# STM32F407VET6.net
KiCad netlist of a schematic drawn in EasyEDA Pro
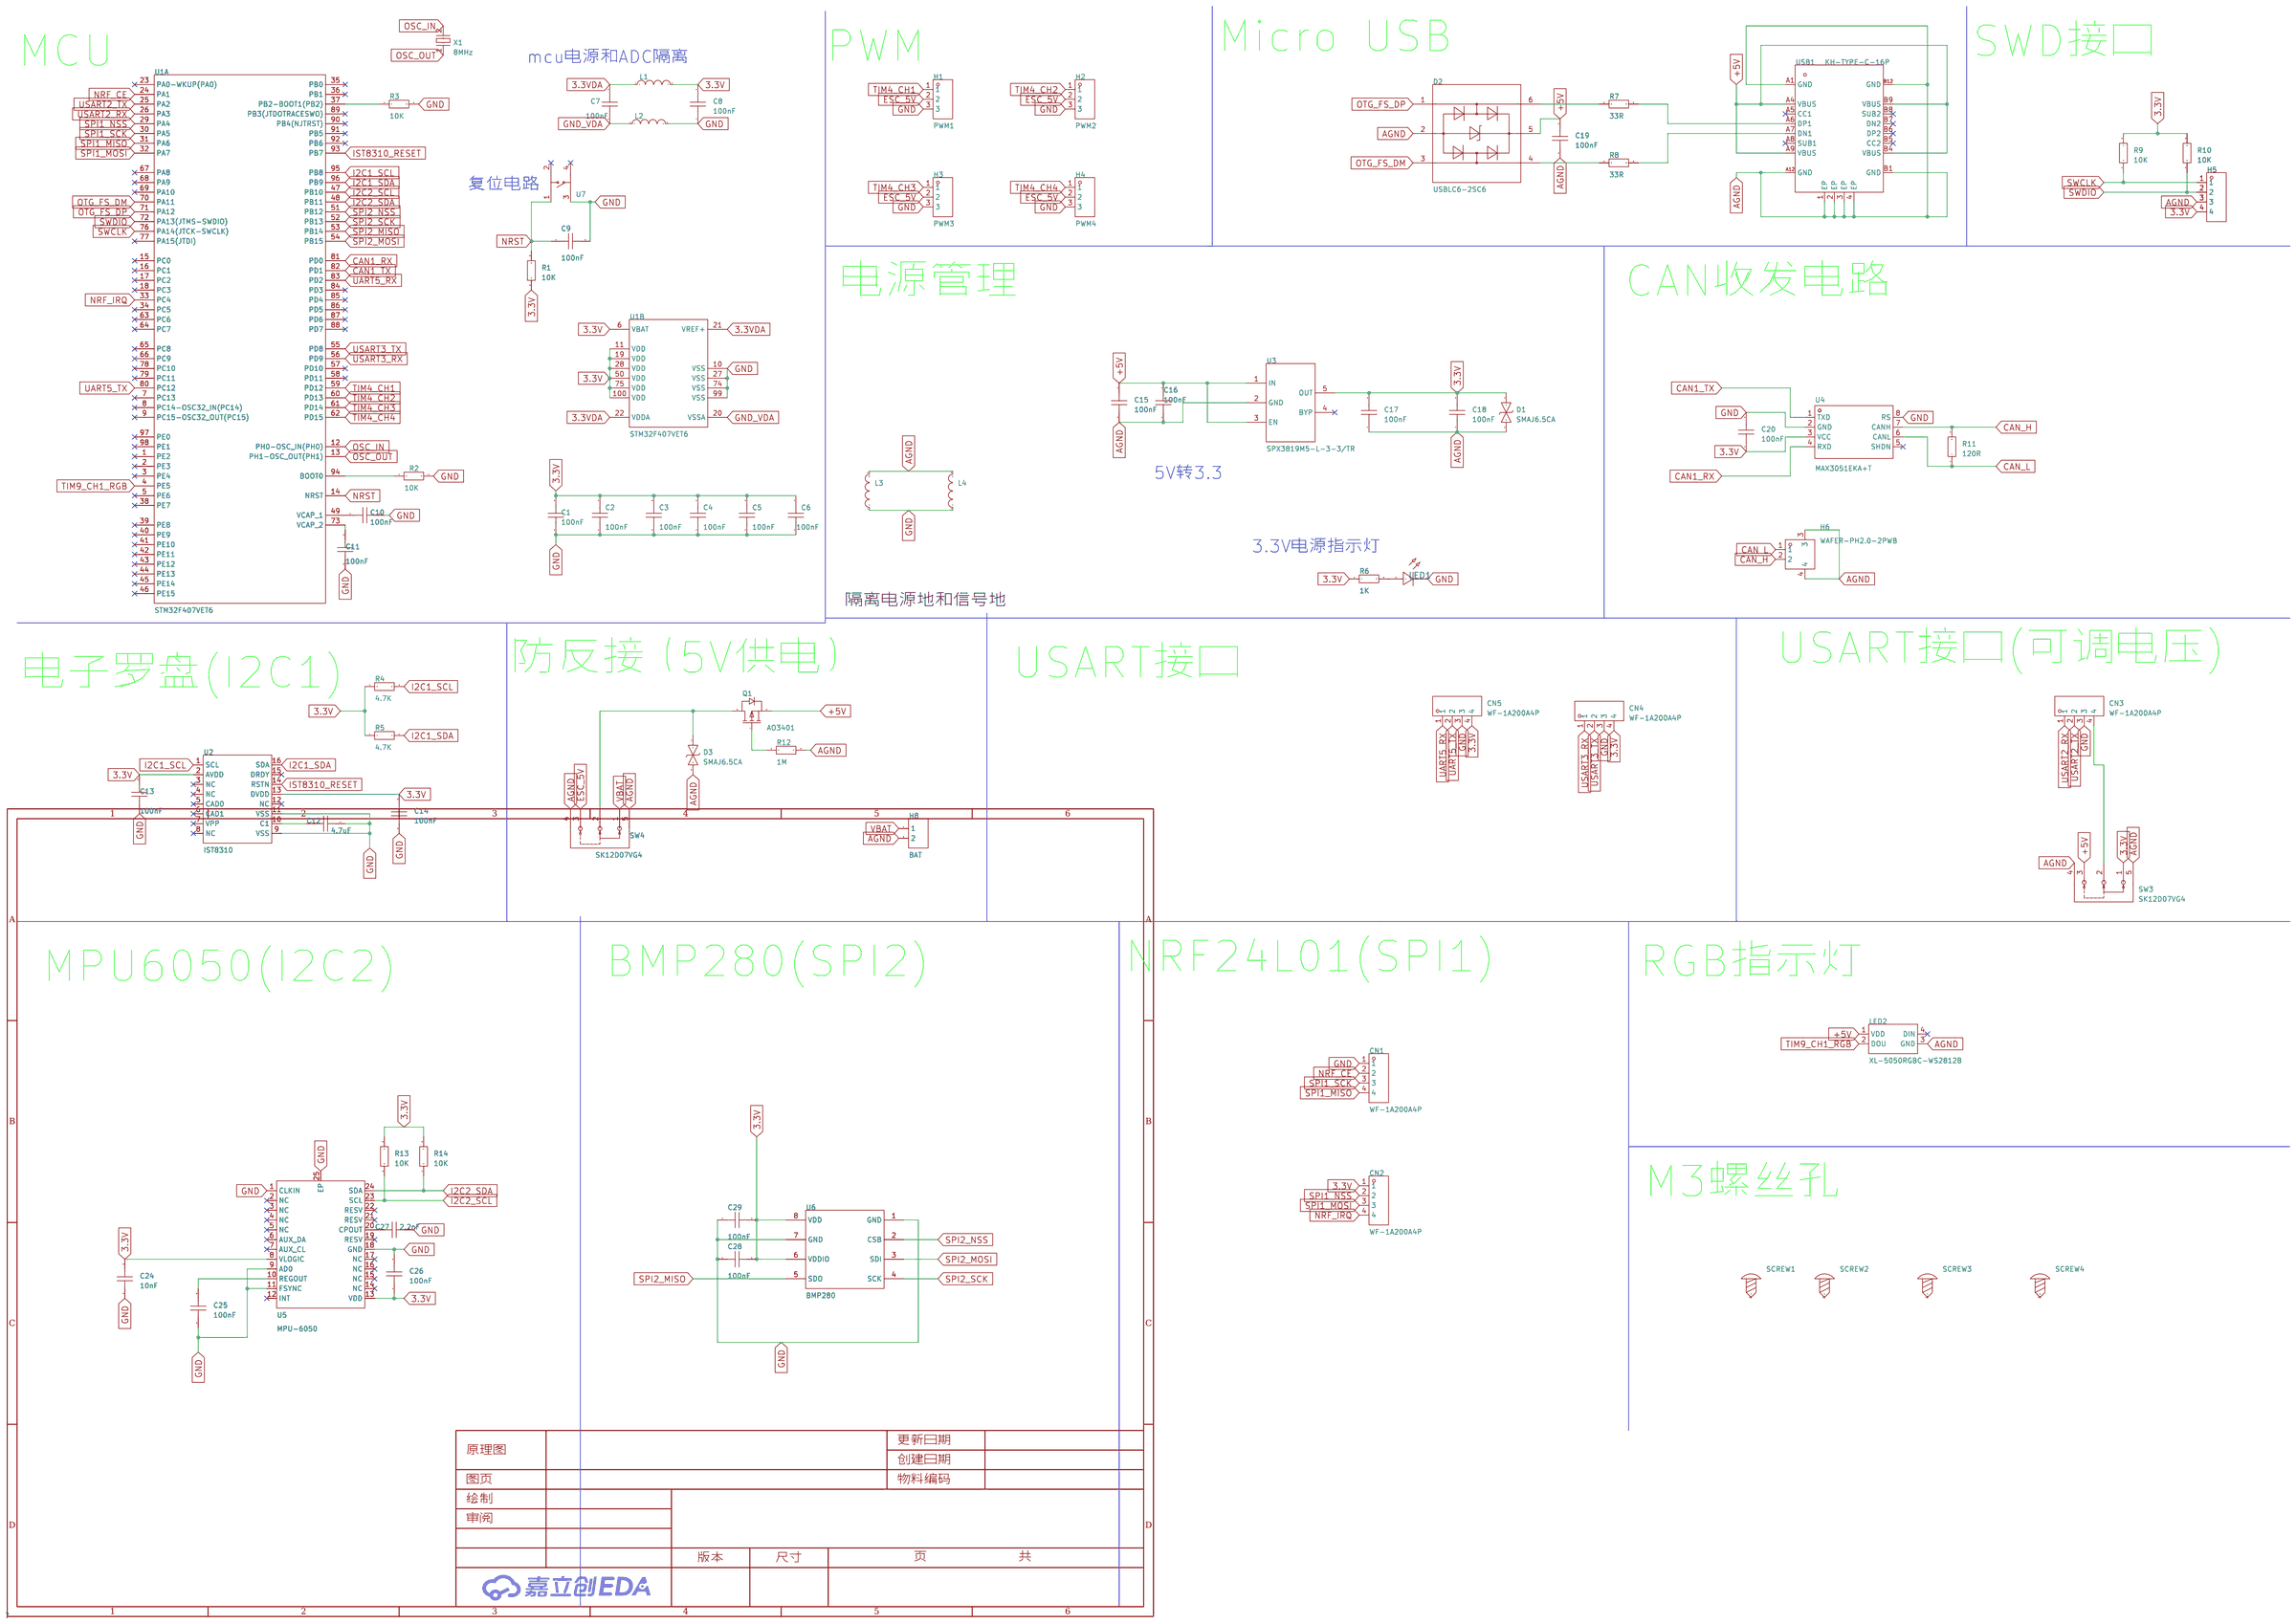
[diagram p0: schematic sheet]

(export (version "E")
  (design (tool "Eeschema 10.0.6"))
  (components
    (comp (ref "C1")
      (value "100nF")
      (footprint "easyedapro:C0603")
      (libsource (lib "easyedapro") (part "CapAcitance"))
    )
    (comp (ref "C2")
      (value "100nF")
      (footprint "easyedapro:C0603")
      (libsource (lib "easyedapro") (part "CapAcitance"))
    )
    (comp (ref "C3")
      (value "100nF")
      (footprint "easyedapro:C0603")
      (libsource (lib "easyedapro") (part "CapAcitance"))
    )
    (comp (ref "C4")
      (value "100nF")
      (footprint "easyedapro:C0603")
      (libsource (lib "easyedapro") (part "CapAcitance"))
    )
    (comp (ref "C5")
      (value "100nF")
      (footprint "easyedapro:C0603")
      (libsource (lib "easyedapro") (part "CapAcitance"))
    )
    (comp (ref "C6")
      (value "100nF")
      (footprint "easyedapro:C0603")
      (libsource (lib "easyedapro") (part "CapAcitance"))
    )
    (comp (ref "C7")
      (value "100nF")
      (footprint "easyedapro:C0603")
      (libsource (lib "easyedapro") (part "CapAcitance"))
    )
    (comp (ref "C8")
      (value "100nF")
      (footprint "easyedapro:C0603")
      (libsource (lib "easyedapro") (part "CapAcitance"))
    )
    (comp (ref "C9")
      (value "100nF")
      (footprint "easyedapro:C0603")
      (libsource (lib "easyedapro") (part "CapAcitance"))
    )
    (comp (ref "C10")
      (value "100nF")
      (footprint "easyedapro:C0603")
      (libsource (lib "easyedapro") (part "CapAcitance"))
    )
    (comp (ref "C11")
      (value "100nF")
      (footprint "easyedapro:C0603")
      (libsource (lib "easyedapro") (part "CapAcitance"))
    )
    (comp (ref "C12")
      (value "4.7uF")
      (footprint "easyedapro:C0603")
      (libsource (lib "easyedapro") (part "CapAcitance"))
    )
    (comp (ref "C13")
      (value "100nF")
      (footprint "easyedapro:C0603")
      (libsource (lib "easyedapro") (part "CapAcitance"))
    )
    (comp (ref "C14")
      (value "100nF")
      (footprint "easyedapro:C0603")
      (libsource (lib "easyedapro") (part "CapAcitance"))
    )
    (comp (ref "C15")
      (value "100nF")
      (footprint "easyedapro:C0603")
      (libsource (lib "easyedapro") (part "CapAcitance"))
    )
    (comp (ref "C16")
      (value "100nF")
      (footprint "easyedapro:C0603")
      (libsource (lib "easyedapro") (part "CapAcitance"))
    )
    (comp (ref "C17")
      (value "100nF")
      (footprint "easyedapro:C0603")
      (libsource (lib "easyedapro") (part "CapAcitance"))
    )
    (comp (ref "C18")
      (value "100nF")
      (footprint "easyedapro:C0603")
      (libsource (lib "easyedapro") (part "CapAcitance"))
    )
    (comp (ref "C19")
      (value "100nF")
      (footprint "easyedapro:C0603")
      (libsource (lib "easyedapro") (part "CapAcitance"))
    )
    (comp (ref "C20")
      (value "100nF")
      (footprint "easyedapro:C0603")
      (libsource (lib "easyedapro") (part "CapAcitance"))
    )
    (comp (ref "C24")
      (value "10nF")
      (footprint "easyedapro:C0603")
      (libsource (lib "easyedapro") (part "CapAcitance"))
    )
    (comp (ref "C25")
      (value "100nF")
      (footprint "easyedapro:C0603")
      (libsource (lib "easyedapro") (part "CapAcitance"))
    )
    (comp (ref "C26")
      (value "100nF")
      (footprint "easyedapro:C0603")
      (libsource (lib "easyedapro") (part "CapAcitance"))
    )
    (comp (ref "C27")
      (value "2.2nF")
      (footprint "easyedapro:C0603")
      (libsource (lib "easyedapro") (part "CapAcitance"))
    )
    (comp (ref "C28")
      (value "100nF")
      (footprint "easyedapro:C0603")
      (libsource (lib "easyedapro") (part "CapAcitance"))
    )
    (comp (ref "C29")
      (value "100nF")
      (footprint "easyedapro:C0603")
      (libsource (lib "easyedapro") (part "CapAcitance"))
    )
    (comp (ref "CN1")
      (value "WF-1A200A4P")
      (footprint "easyedapro:CONN-TH_4P-P2.00_PH2.0-4P-1")
      (description "插针结构:1x4P;间距:2mm;安装方式:直插;参考系列:PH;总PIN数:4P;排数:1;每排PIN数:4;额定电流:2A;触头材质:黄铜;触头镀层:锡;工作温度范围:-25°C~+85°C;")
      (fields (field (name "Manufacturer") "BXCONN(宝讯)"))
      (libsource (lib "easyedapro") (part "WF-1A200A4P"))
    )
    (comp (ref "CN2")
      (value "WF-1A200A4P")
      (footprint "easyedapro:CONN-TH_4P-P2.00_PH2.0-4P-1")
      (description "插针结构:1x4P;间距:2mm;安装方式:直插;参考系列:PH;总PIN数:4P;排数:1;每排PIN数:4;额定电流:2A;触头材质:黄铜;触头镀层:锡;工作温度范围:-25°C~+85°C;")
      (fields (field (name "Manufacturer") "BXCONN(宝讯)"))
      (libsource (lib "easyedapro") (part "WF-1A200A4P"))
    )
    (comp (ref "CN3")
      (value "WF-1A200A4P")
      (footprint "easyedapro:CONN-TH_4P-P2.00_PH2.0-4P-1")
      (description "插针结构:1x4P;间距:2mm;安装方式:直插;参考系列:PH;总PIN数:4P;排数:1;每排PIN数:4;额定电流:2A;触头材质:黄铜;触头镀层:锡;工作温度范围:-25°C~+85°C;")
      (fields (field (name "Manufacturer") "BXCONN(宝讯)"))
      (libsource (lib "easyedapro") (part "WF-1A200A4P"))
    )
    (comp (ref "CN4")
      (value "WF-1A200A4P")
      (footprint "easyedapro:CONN-TH_4P-P2.00_PH2.0-4P-1")
      (description "插针结构:1x4P;间距:2mm;安装方式:直插;参考系列:PH;总PIN数:4P;排数:1;每排PIN数:4;额定电流:2A;触头材质:黄铜;触头镀层:锡;工作温度范围:-25°C~+85°C;")
      (fields (field (name "Manufacturer") "BXCONN(宝讯)"))
      (libsource (lib "easyedapro") (part "WF-1A200A4P"))
    )
    (comp (ref "CN5")
      (value "WF-1A200A4P")
      (footprint "easyedapro:CONN-TH_4P-P2.00_PH2.0-4P-1")
      (description "插针结构:1x4P;间距:2mm;安装方式:直插;参考系列:PH;总PIN数:4P;排数:1;每排PIN数:4;额定电流:2A;触头材质:黄铜;触头镀层:锡;工作温度范围:-25°C~+85°C;")
      (fields (field (name "Manufacturer") "BXCONN(宝讯)"))
      (libsource (lib "easyedapro") (part "WF-1A200A4P"))
    )
    (comp (ref "D1")
      (value "SMAJ6.5CA")
      (footprint "easyedapro:SMA_L4.3-W2.7-LS5.0-BI")
      (description "反向截止电压(Vrwm):6.5V;钳位电压:11.2V;峰值脉冲电流(Ipp):35.7A;峰值脉冲功率(Ppp):400W;击穿电压:7.22V;")
      (fields (field (name "Manufacturer") "GOODWORK(固得沃克)"))
      (libsource (lib "easyedapro") (part "SMAJ6.5CA_C908811"))
    )
    (comp (ref "D2")
      (value "USBLC6-2SC6")
      (footprint "easyedapro:SOT-23-6_L2.9-W1.6-P0.95-LS2.8-BL")
      (description "极性:单向;反向截止电压(Vrwm):5.25V;最大钳位电压:17V;峰值脉冲电流(Ipp)@10/1000us:5A;击穿电压:6V;")
      (fields (field (name "Manufacturer") "ST(意法半导体)"))
      (libsource (lib "easyedapro") (part "USBLC6-2SC6"))
    )
    (comp (ref "D3")
      (value "SMAJ6.5CA")
      (footprint "easyedapro:SMA_L4.3-W2.7-LS5.0-BI")
      (description "反向截止电压(Vrwm):6.5V;钳位电压:11.2V;峰值脉冲电流(Ipp):35.7A;峰值脉冲功率(Ppp):400W;击穿电压:7.22V;")
      (fields (field (name "Manufacturer") "GOODWORK(固得沃克)"))
      (libsource (lib "easyedapro") (part "SMAJ6.5CA_C908811"))
    )
    (comp (ref "H1")
      (value "PWM1")
      (footprint "easyedapro:HDR-TH_3P-P2.54-V-F")
      (libsource (lib "easyedapro") (part "PM254V-11-03-H85"))
    )
    (comp (ref "H2")
      (value "PWM2")
      (footprint "easyedapro:HDR-TH_3P-P2.54-V-F")
      (libsource (lib "easyedapro") (part "PM254V-11-03-H85"))
    )
    (comp (ref "H3")
      (value "PWM3")
      (footprint "easyedapro:HDR-TH_3P-P2.54-V-F")
      (libsource (lib "easyedapro") (part "PM254V-11-03-H85"))
    )
    (comp (ref "H4")
      (value "PWM4")
      (footprint "easyedapro:HDR-TH_3P-P2.54-V-F")
      (libsource (lib "easyedapro") (part "PM254V-11-03-H85"))
    )
    (comp (ref "H5")
      (value "~")
      (footprint "easyedapro:HDR-TH_4P-P2.54-V-F")
      (libsource (lib "easyedapro") (part "2.54-1*4P母"))
    )
    (comp (ref "H6")
      (value "WAFER-PH2.0-2PWB")
      (footprint "easyedapro:CONN-SMD_2P-P2.00_XUNPU_WAFER-PH2.0-2PWB")
      (fields (field (name "Manufacturer") "XUNPU(讯普)"))
      (libsource (lib "easyedapro") (part "WAFER-PH2.0-2PWB"))
    )
    (comp (ref "H8")
      (value "BAT")
      (footprint "easyedapro:HDR-TH_2P-P2.54-V-F")
      (libsource (lib "easyedapro") (part "Header-Female-2.54_1x2"))
    )
    (comp (ref "L1")
      (value "CBG160808U000T")
      (footprint "easyedapro:L0603")
      (description "标称阻抗@测试频率:0Ω@100MHz;直流电阻(RDC):100mΩ;")
      (fields (field (name "Manufacturer") "FH(风华)"))
      (libsource (lib "easyedapro") (part "CBG160808U000T"))
    )
    (comp (ref "L2")
      (value "CBG160808U000T")
      (footprint "easyedapro:L0603")
      (description "标称阻抗@测试频率:0Ω@100MHz;直流电阻(RDC):100mΩ;")
      (fields (field (name "Manufacturer") "FH(风华)"))
      (libsource (lib "easyedapro") (part "CBG160808U000T"))
    )
    (comp (ref "L3")
      (value "CBG160808U000T")
      (footprint "easyedapro:L0603")
      (description "标称阻抗@测试频率:0Ω@100MHz;直流电阻(RDC):100mΩ;")
      (fields (field (name "Manufacturer") "FH(风华)"))
      (libsource (lib "easyedapro") (part "CBG160808U000T"))
    )
    (comp (ref "L4")
      (value "CBG160808U000T")
      (footprint "easyedapro:L0603")
      (description "标称阻抗@测试频率:0Ω@100MHz;直流电阻(RDC):100mΩ;")
      (fields (field (name "Manufacturer") "FH(风华)"))
      (libsource (lib "easyedapro") (part "CBG160808U000T"))
    )
    (comp (ref "LED1")
      (value "~")
      (footprint "easyedapro:LED_0603")
      (libsource (lib "easyedapro") (part "LED_R"))
    )
    (comp (ref "LED2")
      (value "XL-5050RGBC-WS2812B")
      (footprint "easyedapro:LED-SMD_4P-L5.0-W5.0-BL_XL-5050RGBC")
      (description "5050七彩幻彩透明贴片LED灯珠 5050 幻彩透明四脚 ws2812B 内置驱动IC")
      (fields (field (name "Manufacturer") "XINGLIGHT(成兴光)"))
      (libsource (lib "easyedapro") (part "XL-5050RGBC-WS2812B"))
    )
    (comp (ref "Q1")
      (value "AO3401")
      (footprint "easyedapro:SOT-23-3_L2.9-W1.4-P1.90-LS2.6-BR")
      (fields (field (name "Manufacturer") "TWGMC(台湾迪嘉)"))
      (libsource (lib "easyedapro") (part "AO3401_C727156"))
    )
    (comp (ref "R1") (value "10K") (footprint "easyedapro:R0603") (libsource (lib "easyedapro") (part "电阻")))
    (comp (ref "R2") (value "10K") (footprint "easyedapro:R0603") (libsource (lib "easyedapro") (part "电阻")))
    (comp (ref "R3") (value "10K") (footprint "easyedapro:R0603") (libsource (lib "easyedapro") (part "电阻")))
    (comp (ref "R4") (value "4.7K") (footprint "easyedapro:R0603") (libsource (lib "easyedapro") (part "电阻")))
    (comp (ref "R5") (value "4.7K") (footprint "easyedapro:R0603") (libsource (lib "easyedapro") (part "电阻")))
    (comp (ref "R6") (value "1K") (footprint "easyedapro:R0603") (libsource (lib "easyedapro") (part "电阻")))
    (comp (ref "R7") (value "33R") (footprint "easyedapro:R0603") (libsource (lib "easyedapro") (part "电阻")))
    (comp (ref "R8") (value "33R") (footprint "easyedapro:R0603") (libsource (lib "easyedapro") (part "电阻")))
    (comp (ref "R9") (value "10K") (footprint "easyedapro:R0603") (libsource (lib "easyedapro") (part "电阻")))
    (comp (ref "R10") (value "10K") (footprint "easyedapro:R0603") (libsource (lib "easyedapro") (part "电阻")))
    (comp (ref "R11")
      (value "120R")
      (footprint "easyedapro:R0603")
      (libsource (lib "easyedapro") (part "电阻"))
    )
    (comp (ref "R12") (value "1M") (footprint "easyedapro:R0603") (libsource (lib "easyedapro") (part "电阻")))
    (comp (ref "R13") (value "10K") (footprint "easyedapro:R0603") (libsource (lib "easyedapro") (part "电阻")))
    (comp (ref "R14") (value "10K") (footprint "easyedapro:R0603") (libsource (lib "easyedapro") (part "电阻")))
    (comp (ref "SCREW1")
      (value "~")
      (footprint "easyedapro:M3螺丝")
      (libsource (lib "easyedapro") (part "螺丝孔"))
    )
    (comp (ref "SCREW2")
      (value "~")
      (footprint "easyedapro:M3螺丝")
      (libsource (lib "easyedapro") (part "螺丝孔"))
    )
    (comp (ref "SCREW3")
      (value "~")
      (footprint "easyedapro:M3螺丝")
      (libsource (lib "easyedapro") (part "螺丝孔"))
    )
    (comp (ref "SCREW4")
      (value "~")
      (footprint "easyedapro:M3螺丝")
      (libsource (lib "easyedapro") (part "螺丝孔"))
    )
    (comp (ref "SW3")
      (value "SK12D07VG4")
      (footprint "easyedapro:SW-TH_SK12D07VG4")
      (description "电路结构:单刀双掷;安装方式:-;额定电流(DC):500mA;额定电压(DC):50V;额定电流(AC):-;额定电压(AC):-;机械寿命:5千次;")
      (fields (field (name "Manufacturer") "SHOU HAN(首韩)"))
      (libsource (lib "easyedapro") (part "SK12D07VG4"))
    )
    (comp (ref "SW4")
      (value "SK12D07VG4")
      (footprint "easyedapro:SW-TH_SK12D07VG4")
      (description "电路结构:单刀双掷;安装方式:-;额定电流(DC):500mA;额定电压(DC):50V;额定电流(AC):-;额定电压(AC):-;机械寿命:5千次;")
      (fields (field (name "Manufacturer") "SHOU HAN(首韩)"))
      (libsource (lib "easyedapro") (part "SK12D07VG4"))
    )
    (comp (ref "U1")
      (value "STM32F407VET6")
      (footprint "easyedapro:LQFP-100_L14.0-W14.0-P0.50-LS16.0-BL")
      (description "CPU内核:ARM-M4;CPU最大主频:168MHz;应用领域:-;")
      (fields (field (name "Manufacturer") "ST(意法半导体)"))
      (libsource (lib "easyedapro") (part "STM32F407VET6"))
    )
    (comp (ref "U2")
      (value "IST8310")
      (footprint "easyedapro:LGA-16_L3.0-W3.0-P0.50-BL_SQ")
      (fields (field (name "Manufacturer") "iSentek(爱盛科技)"))
      (libsource (lib "easyedapro") (part "IST8310_C2683055"))
    )
    (comp (ref "U3")
      (value "SPX3819M5-L-3-3/TR")
      (footprint "easyedapro:SOT-23-5_L3.0-W1.7-P0.95-LS2.8-BL")
      (description "输出类型:固定;工作电压:16V;输出电压:3.3V;输出电流:500mA;电源纹波抑制比(PSRR):70dB;输出极性:正极;")
      (fields (field (name "Manufacturer") "MaxLinear(迈凌)"))
      (libsource (lib "easyedapro") (part "SPX3819M5-L-3-3/TR"))
    )
    (comp (ref "U4")
      (value "MAX3051EKA+T")
      (footprint "easyedapro:SOT-23-8_L3.0-W1.7-P0.65-LS2.8-TL")
      (description "类型:CAN收发器;数据速率:1Mbps;")
      (fields (field (name "Manufacturer") "ADI(亚德诺)/MAXIM(美信)"))
      (libsource (lib "easyedapro") (part "MAX3051EKA+T"))
    )
    (comp (ref "U5")
      (value "MPU-6050")
      (footprint "easyedapro:QFN-24_L4.0-W4.0-P0.50-BL-EP2.7")
      (description "传感器类型:加速度计陀螺仪;")
      (fields (field (name "Manufacturer") "TDK InvenSense(应美盛)"))
      (libsource (lib "easyedapro") (part "MPU-6050_C24112"))
    )
    (comp (ref "U6")
      (value "BMP280")
      (footprint "easyedapro:LGA-8_L2.5-W2.0-P0.65_AMP6127")
      (description "Bosch气压传感器新品，可测量大气压力，带高精度温度测量，可校准精确计算海拔高度。I2C或SPI接口，宽量程（300-1100hpa），精度高")
      (fields (field (name "Manufacturer") "Bosch(博世)"))
      (libsource (lib "easyedapro") (part "BMP280"))
    )
    (comp (ref "U7")
      (value "TPS645-5NC60")
      (footprint "easyedapro:SW-SMD_4P-L6.0-W6.0-P4.50-LS9.2")
      (fields (field (name "Manufacturer") "ROCPU Switches(台普)"))
      (libsource (lib "easyedapro") (part "TPS645-5NC60"))
    )
    (comp (ref "USB1")
      (value "KH-TYPE-C-16P")
      (footprint "easyedapro:USB-C-SMD_KH-TYPE-C-16P")
      (description "连接器类型:Type-C;标准:-;公母:母;端口数量:1;触点数量:16P;安装方式:卧贴;额定电流 - 电源:3A;工作温度范围:-40°C~+85°C;")
      (fields (field (name "Manufacturer") "kinghelm(金航标)"))
      (libsource (lib "easyedapro") (part "KH-TYPE-C-16P"))
    )
    (comp (ref "X1")
      (value "8MHz")
      (footprint "easyedapro:OSC-SMD_2P-L3.2-W2.5")
      (description "晶振类型:-;频率:8MHz;常温频差:±50ppm;外接负载电容:8pF;频率稳定度(全温):±150ppm;")
      (fields
        (field (name "Manufacturer Part") "NX3225GD-8MHZ-STD-CRA-3")
        (field (name "Manufacturer") "NDK")
      )
      (libsource (lib "easyedapro") (part "NX3225GD-8MHZ-STD-CRA-3"))
    )
  )
  (nets
    (net (code "1") (name "+5V") (class "Default")
      (node (ref "C15") (pin "2") (pinfunction "2_2") (pintype "input"))
      (node (ref "C16") (pin "2") (pinfunction "2_2") (pintype "input"))
      (node (ref "C19") (pin "2") (pinfunction "2_2") (pintype "input"))
      (node (ref "D2") (pin "5") (pinfunction "5_5") (pintype "input"))
      (node (ref "LED2") (pin "1") (pinfunction "VDD_1") (pintype "unspecified"))
      (node (ref "Q1") (pin "2") (pinfunction "S_2") (pintype "unspecified"))
      (node (ref "SW3") (pin "3") (pinfunction "3_3") (pintype "unspecified"))
      (node (ref "U3") (pin "1") (pinfunction "IN_1") (pintype "unspecified"))
      (node (ref "U3") (pin "3") (pinfunction "EN_3") (pintype "unspecified"))
      (node (ref "USB1") (pin "A4") (pinfunction "VBUS_A4") (pintype "unspecified"))
      (node (ref "USB1") (pin "A9") (pinfunction "VBUS_A9") (pintype "unspecified"))
      (node (ref "USB1") (pin "B4") (pinfunction "VBUS_B4") (pintype "unspecified"))
      (node (ref "USB1") (pin "B9") (pinfunction "VBUS_B9") (pintype "unspecified"))
    )
    (net (code "2") (name "3.3V") (class "Default")
      (node (ref "C1") (pin "2") (pinfunction "2_2") (pintype "input"))
      (node (ref "C13") (pin "2") (pinfunction "2_2") (pintype "input"))
      (node (ref "C14") (pin "2") (pinfunction "2_2") (pintype "input"))
      (node (ref "C17") (pin "2") (pinfunction "2_2") (pintype "input"))
      (node (ref "C18") (pin "2") (pinfunction "2_2") (pintype "input"))
      (node (ref "C2") (pin "2") (pinfunction "2_2") (pintype "input"))
      (node (ref "C20") (pin "1") (pinfunction "1_1") (pintype "input"))
      (node (ref "C24") (pin "2") (pinfunction "2_2") (pintype "input"))
      (node (ref "C26") (pin "1") (pinfunction "1_1") (pintype "input"))
      (node (ref "C28") (pin "2") (pinfunction "2_2") (pintype "input"))
      (node (ref "C29") (pin "2") (pinfunction "2_2") (pintype "input"))
      (node (ref "C3") (pin "2") (pinfunction "2_2") (pintype "input"))
      (node (ref "C4") (pin "2") (pinfunction "2_2") (pintype "input"))
      (node (ref "C5") (pin "2") (pinfunction "2_2") (pintype "input"))
      (node (ref "C6") (pin "2") (pinfunction "2_2") (pintype "input"))
      (node (ref "C8") (pin "2") (pinfunction "2_2") (pintype "input"))
      (node (ref "CN2") (pin "1") (pinfunction "1_1") (pintype "unspecified"))
      (node (ref "CN4") (pin "4") (pinfunction "4_4") (pintype "unspecified"))
      (node (ref "CN5") (pin "4") (pinfunction "4_4") (pintype "unspecified"))
      (node (ref "D1") (pin "1") (pinfunction "1_1") (pintype "unspecified"))
      (node (ref "H5") (pin "4") (pinfunction "4_4") (pintype "unspecified"))
      (node (ref "L1") (pin "2") (pinfunction "2_2") (pintype "unspecified"))
      (node (ref "R1") (pin "1") (pinfunction "1_1") (pintype "input"))
      (node (ref "R10") (pin "2") (pinfunction "2_2") (pintype "input"))
      (node (ref "R13") (pin "2") (pinfunction "2_2") (pintype "input"))
      (node (ref "R14") (pin "2") (pinfunction "2_2") (pintype "input"))
      (node (ref "R4") (pin "1") (pinfunction "1_1") (pintype "input"))
      (node (ref "R5") (pin "1") (pinfunction "1_1") (pintype "input"))
      (node (ref "R6") (pin "1") (pinfunction "1_1") (pintype "input"))
      (node (ref "R9") (pin "2") (pinfunction "2_2") (pintype "input"))
      (node (ref "SW3") (pin "1") (pinfunction "1_1") (pintype "unspecified"))
      (node (ref "U1") (pin "100") (pinfunction "VDD_100") (pintype "unspecified"))
      (node (ref "U1") (pin "11") (pinfunction "VDD_11") (pintype "unspecified"))
      (node (ref "U1") (pin "19") (pinfunction "VDD_19") (pintype "unspecified"))
      (node (ref "U1") (pin "28") (pinfunction "VDD_28") (pintype "unspecified"))
      (node (ref "U1") (pin "50") (pinfunction "VDD_50") (pintype "unspecified"))
      (node (ref "U1") (pin "6") (pinfunction "VBAT_6") (pintype "unspecified"))
      (node (ref "U1") (pin "75") (pinfunction "VDD_75") (pintype "unspecified"))
      (node (ref "U2") (pin "13") (pinfunction "DVDD_13") (pintype "unspecified"))
      (node (ref "U2") (pin "2") (pinfunction "AVDD_2") (pintype "unspecified"))
      (node (ref "U3") (pin "5") (pinfunction "OUT_5") (pintype "unspecified"))
      (node (ref "U4") (pin "3") (pinfunction "VCC_3") (pintype "unspecified"))
      (node (ref "U5") (pin "13") (pinfunction "VDD_13") (pintype "unspecified"))
      (node (ref "U5") (pin "8") (pinfunction "VLOGIC_8") (pintype "unspecified"))
      (node (ref "U6") (pin "6") (pinfunction "VDDIO_6") (pintype "unspecified"))
      (node (ref "U6") (pin "8") (pinfunction "VDD_8") (pintype "unspecified"))
    )
    (net (code "3") (name "3.3VDA") (class "Default")
      (node (ref "C7") (pin "2") (pinfunction "2_2") (pintype "input"))
      (node (ref "L1") (pin "1") (pinfunction "1_1") (pintype "unspecified"))
      (node (ref "U1") (pin "21") (pinfunction "VREF+_21") (pintype "unspecified"))
      (node (ref "U1") (pin "22") (pinfunction "VDDA_22") (pintype "unspecified"))
    )
    (net (code "4") (name "AGND") (class "Default")
      (node (ref "C15") (pin "1") (pinfunction "1_1") (pintype "input"))
      (node (ref "C16") (pin "1") (pinfunction "1_1") (pintype "input"))
      (node (ref "C17") (pin "1") (pinfunction "1_1") (pintype "input"))
      (node (ref "C18") (pin "1") (pinfunction "1_1") (pintype "input"))
      (node (ref "C19") (pin "1") (pinfunction "1_1") (pintype "input"))
      (node (ref "D1") (pin "2") (pinfunction "2_2") (pintype "unspecified"))
      (node (ref "D2") (pin "2") (pinfunction "2_2") (pintype "input"))
      (node (ref "D3") (pin "2") (pinfunction "2_2") (pintype "unspecified"))
      (node (ref "H5") (pin "3") (pinfunction "3_3") (pintype "unspecified"))
      (node (ref "H6") (pin "3") (pinfunction "3_3") (pintype "unspecified"))
      (node (ref "H6") (pin "4") (pinfunction "4_4") (pintype "unspecified"))
      (node (ref "H8") (pin "2") (pinfunction "2_2") (pintype "input"))
      (node (ref "L3") (pin "2") (pinfunction "2_2") (pintype "unspecified"))
      (node (ref "L4") (pin "2") (pinfunction "2_2") (pintype "unspecified"))
      (node (ref "LED2") (pin "3") (pinfunction "GND_3") (pintype "unspecified"))
      (node (ref "R12") (pin "2") (pinfunction "2_2") (pintype "input"))
      (node (ref "SW3") (pin "4") (pinfunction "4_4") (pintype "unspecified"))
      (node (ref "SW3") (pin "5") (pinfunction "5_5") (pintype "unspecified"))
      (node (ref "SW4") (pin "4") (pinfunction "4_4") (pintype "unspecified"))
      (node (ref "SW4") (pin "5") (pinfunction "5_5") (pintype "unspecified"))
      (node (ref "U3") (pin "2") (pinfunction "GND_2") (pintype "unspecified"))
      (node (ref "USB1") (pin "1") (pinfunction "EP_1") (pintype "unspecified"))
      (node (ref "USB1") (pin "2") (pinfunction "EP_2") (pintype "unspecified"))
      (node (ref "USB1") (pin "3") (pinfunction "EP_3") (pintype "unspecified"))
      (node (ref "USB1") (pin "4") (pinfunction "EP_4") (pintype "unspecified"))
      (node (ref "USB1") (pin "A1") (pinfunction "GND_A1") (pintype "unspecified"))
      (node (ref "USB1") (pin "A12") (pinfunction "GND_A12") (pintype "unspecified"))
      (node (ref "USB1") (pin "B1") (pinfunction "GND_B1") (pintype "unspecified"))
      (node (ref "USB1") (pin "B12") (pinfunction "GND_B12") (pintype "unspecified"))
    )
    (net (code "5") (name "CAN1_RX") (class "Default")
      (node (ref "U1") (pin "81") (pinfunction "PD0_81") (pintype "bidirectional"))
      (node (ref "U4") (pin "4") (pinfunction "RXD_4") (pintype "unspecified"))
    )
    (net (code "6") (name "CAN1_TX") (class "Default")
      (node (ref "U1") (pin "82") (pinfunction "PD1_82") (pintype "bidirectional"))
      (node (ref "U4") (pin "1") (pinfunction "TXD_1") (pintype "unspecified"))
    )
    (net (code "7") (name "CAN_H") (class "Default")
      (node (ref "H6") (pin "2") (pinfunction "2_2") (pintype "unspecified"))
      (node (ref "R11") (pin "2") (pinfunction "2_2") (pintype "input"))
      (node (ref "U4") (pin "7") (pinfunction "CANH_7") (pintype "unspecified"))
    )
    (net (code "8") (name "CAN_L") (class "Default")
      (node (ref "H6") (pin "1") (pinfunction "1_1") (pintype "unspecified"))
      (node (ref "R11") (pin "1") (pinfunction "1_1") (pintype "input"))
      (node (ref "U4") (pin "6") (pinfunction "CANL_6") (pintype "unspecified"))
    )
    (net (code "9") (name "ESC_5V") (class "Default")
      (node (ref "H1") (pin "2") (pinfunction "2_2") (pintype "unspecified"))
      (node (ref "H2") (pin "2") (pinfunction "2_2") (pintype "unspecified"))
      (node (ref "H3") (pin "2") (pinfunction "2_2") (pintype "unspecified"))
      (node (ref "H4") (pin "2") (pinfunction "2_2") (pintype "unspecified"))
      (node (ref "SW4") (pin "3") (pinfunction "3_3") (pintype "unspecified"))
    )
    (net (code "10") (name "GND") (class "Default")
      (node (ref "C1") (pin "1") (pinfunction "1_1") (pintype "input"))
      (node (ref "C10") (pin "2") (pinfunction "2_2") (pintype "input"))
      (node (ref "C11") (pin "2") (pinfunction "2_2") (pintype "input"))
      (node (ref "C12") (pin "2") (pinfunction "2_2") (pintype "input"))
      (node (ref "C13") (pin "1") (pinfunction "1_1") (pintype "input"))
      (node (ref "C14") (pin "1") (pinfunction "1_1") (pintype "input"))
      (node (ref "C2") (pin "1") (pinfunction "1_1") (pintype "input"))
      (node (ref "C20") (pin "2") (pinfunction "2_2") (pintype "input"))
      (node (ref "C24") (pin "1") (pinfunction "1_1") (pintype "input"))
      (node (ref "C25") (pin "1") (pinfunction "1_1") (pintype "input"))
      (node (ref "C26") (pin "2") (pinfunction "2_2") (pintype "input"))
      (node (ref "C27") (pin "2") (pinfunction "2_2") (pintype "input"))
      (node (ref "C28") (pin "1") (pinfunction "1_1") (pintype "input"))
      (node (ref "C29") (pin "1") (pinfunction "1_1") (pintype "input"))
      (node (ref "C3") (pin "1") (pinfunction "1_1") (pintype "input"))
      (node (ref "C4") (pin "1") (pinfunction "1_1") (pintype "input"))
      (node (ref "C5") (pin "1") (pinfunction "1_1") (pintype "input"))
      (node (ref "C6") (pin "1") (pinfunction "1_1") (pintype "input"))
      (node (ref "C8") (pin "1") (pinfunction "1_1") (pintype "input"))
      (node (ref "C9") (pin "2") (pinfunction "2_2") (pintype "input"))
      (node (ref "CN1") (pin "1") (pinfunction "1_1") (pintype "unspecified"))
      (node (ref "CN3") (pin "3") (pinfunction "3_3") (pintype "unspecified"))
      (node (ref "CN4") (pin "3") (pinfunction "3_3") (pintype "unspecified"))
      (node (ref "CN5") (pin "3") (pinfunction "3_3") (pintype "unspecified"))
      (node (ref "H1") (pin "3") (pinfunction "3_3") (pintype "unspecified"))
      (node (ref "H2") (pin "3") (pinfunction "3_3") (pintype "unspecified"))
      (node (ref "H3") (pin "3") (pinfunction "3_3") (pintype "unspecified"))
      (node (ref "H4") (pin "3") (pinfunction "3_3") (pintype "unspecified"))
      (node (ref "L2") (pin "2") (pinfunction "2_2") (pintype "unspecified"))
      (node (ref "L3") (pin "1") (pinfunction "1_1") (pintype "unspecified"))
      (node (ref "L4") (pin "1") (pinfunction "1_1") (pintype "unspecified"))
      (node (ref "LED1") (pin "1") (pinfunction "C_1") (pintype "input"))
      (node (ref "R2") (pin "2") (pinfunction "2_2") (pintype "input"))
      (node (ref "R3") (pin "2") (pinfunction "2_2") (pintype "input"))
      (node (ref "U1") (pin "10") (pinfunction "VSS_10") (pintype "unspecified"))
      (node (ref "U1") (pin "27") (pinfunction "VSS_27") (pintype "unspecified"))
      (node (ref "U1") (pin "74") (pinfunction "VSS_74") (pintype "unspecified"))
      (node (ref "U1") (pin "99") (pinfunction "VSS_99") (pintype "unspecified"))
      (node (ref "U2") (pin "11") (pinfunction "VSS_11") (pintype "unspecified"))
      (node (ref "U2") (pin "9") (pinfunction "VSS_9") (pintype "unspecified"))
      (node (ref "U4") (pin "2") (pinfunction "GND_2") (pintype "unspecified"))
      (node (ref "U4") (pin "8") (pinfunction "RS_8") (pintype "unspecified"))
      (node (ref "U5") (pin "1") (pinfunction "CLKIN_1") (pintype "unspecified"))
      (node (ref "U5") (pin "11") (pinfunction "FSYNC_11") (pintype "unspecified"))
      (node (ref "U5") (pin "18") (pinfunction "GND_18") (pintype "unspecified"))
      (node (ref "U5") (pin "25") (pinfunction "EP_25") (pintype "unspecified"))
      (node (ref "U5") (pin "9") (pinfunction "AD0_9") (pintype "unspecified"))
      (node (ref "U6") (pin "1") (pinfunction "GND_1") (pintype "unspecified"))
      (node (ref "U6") (pin "7") (pinfunction "GND_7") (pintype "unspecified"))
      (node (ref "U7") (pin "3") (pinfunction "3_3") (pintype "unspecified"))
    )
    (net (code "11") (name "GND_VDA") (class "Default")
      (node (ref "C7") (pin "1") (pinfunction "1_1") (pintype "input"))
      (node (ref "L2") (pin "1") (pinfunction "1_1") (pintype "unspecified"))
      (node (ref "U1") (pin "20") (pinfunction "VSSA_20") (pintype "unspecified"))
    )
    (net (code "12") (name "I2C1_SCL") (class "Default")
      (node (ref "R4") (pin "2") (pinfunction "2_2") (pintype "input"))
      (node (ref "U1") (pin "95") (pinfunction "PB8_95") (pintype "bidirectional"))
      (node (ref "U2") (pin "1") (pinfunction "SCL_1") (pintype "unspecified"))
    )
    (net (code "13") (name "I2C1_SDA") (class "Default")
      (node (ref "R5") (pin "2") (pinfunction "2_2") (pintype "input"))
      (node (ref "U1") (pin "96") (pinfunction "PB9_96") (pintype "bidirectional"))
      (node (ref "U2") (pin "16") (pinfunction "SDA_16") (pintype "unspecified"))
    )
    (net (code "14") (name "I2C2_SCL") (class "Default")
      (node (ref "R13") (pin "1") (pinfunction "1_1") (pintype "input"))
      (node (ref "U1") (pin "47") (pinfunction "PB10_47") (pintype "bidirectional"))
      (node (ref "U5") (pin "23") (pinfunction "SCL_23") (pintype "unspecified"))
    )
    (net (code "15") (name "I2C2_SDA") (class "Default")
      (node (ref "R14") (pin "1") (pinfunction "1_1") (pintype "input"))
      (node (ref "U1") (pin "48") (pinfunction "PB11_48") (pintype "bidirectional"))
      (node (ref "U5") (pin "24") (pinfunction "SDA_24") (pintype "unspecified"))
    )
    (net (code "16") (name "IST8310_RESET") (class "Default")
      (node (ref "U1") (pin "93") (pinfunction "PB7_93") (pintype "bidirectional"))
      (node (ref "U2") (pin "14") (pinfunction "RSTN_14") (pintype "unspecified"))
    )
    (net (code "17") (name "NRF_CE") (class "Default")
      (node (ref "CN1") (pin "2") (pinfunction "2_2") (pintype "unspecified"))
      (node (ref "U1") (pin "24") (pinfunction "PA1_24") (pintype "bidirectional"))
    )
    (net (code "18") (name "NRF_IRQ") (class "Default")
      (node (ref "CN2") (pin "4") (pinfunction "4_4") (pintype "unspecified"))
      (node (ref "U1") (pin "33") (pinfunction "PC4_33") (pintype "bidirectional"))
    )
    (net (code "19") (name "NRST") (class "Default")
      (node (ref "C9") (pin "1") (pinfunction "1_1") (pintype "input"))
      (node (ref "R1") (pin "2") (pinfunction "2_2") (pintype "input"))
      (node (ref "U1") (pin "14") (pinfunction "NRST_14") (pintype "bidirectional"))
      (node (ref "U7") (pin "1") (pinfunction "1_1") (pintype "unspecified"))
    )
    (net (code "20") (name "Net-(CN3-Pad4)") (class "Default")
      (node (ref "CN3") (pin "4") (pinfunction "4_4") (pintype "unspecified"))
      (node (ref "SW3") (pin "2") (pinfunction "2_2") (pintype "unspecified"))
    )
    (net (code "21") (name "Net-(D2-Pad4)") (class "Default")
      (node (ref "D2") (pin "4") (pinfunction "4_4") (pintype "input"))
      (node (ref "R8") (pin "1") (pinfunction "1_1") (pintype "input"))
    )
    (net (code "22") (name "Net-(D2-Pad6)") (class "Default")
      (node (ref "D2") (pin "6") (pinfunction "6_6") (pintype "input"))
      (node (ref "R7") (pin "1") (pinfunction "1_1") (pintype "input"))
    )
    (net (code "23") (name "Net-(LED1-A)") (class "Default")
      (node (ref "LED1") (pin "2") (pinfunction "A_2") (pintype "input"))
      (node (ref "R6") (pin "2") (pinfunction "2_2") (pintype "input"))
    )
    (net (code "24") (name "Net-(Q1-D)") (class "Default")
      (node (ref "D3") (pin "1") (pinfunction "1_1") (pintype "unspecified"))
      (node (ref "Q1") (pin "3") (pinfunction "D_3") (pintype "unspecified"))
      (node (ref "SW4") (pin "2") (pinfunction "2_2") (pintype "unspecified"))
    )
    (net (code "25") (name "Net-(Q1-G)") (class "Default")
      (node (ref "Q1") (pin "1") (pinfunction "G_1") (pintype "unspecified"))
      (node (ref "R12") (pin "1") (pinfunction "1_1") (pintype "input"))
    )
    (net (code "26") (name "Net-(U1A-BOOT0)") (class "Default")
      (node (ref "R2") (pin "1") (pinfunction "1_1") (pintype "input"))
      (node (ref "U1") (pin "94") (pinfunction "BOOT0_94") (pintype "unspecified"))
    )
    (net (code "27") (name "Net-(U1A-PB2-BOOT1(PB2))") (class "Default")
      (node (ref "R3") (pin "1") (pinfunction "1_1") (pintype "input"))
      (node (ref "U1") (pin "37") (pinfunction "PB2-BOOT1(PB2)_37") (pintype "bidirectional"))
    )
    (net (code "28") (name "Net-(U1A-VCAP_1)") (class "Default")
      (node (ref "C10") (pin "1") (pinfunction "1_1") (pintype "input"))
      (node (ref "U1") (pin "49") (pinfunction "VCAP_1_49") (pintype "unspecified"))
    )
    (net (code "29") (name "Net-(U1A-VCAP_2)") (class "Default")
      (node (ref "C11") (pin "1") (pinfunction "1_1") (pintype "input"))
      (node (ref "U1") (pin "73") (pinfunction "VCAP_2_73") (pintype "unspecified"))
    )
    (net (code "30") (name "Net-(U2-C1)") (class "Default")
      (node (ref "C12") (pin "1") (pinfunction "1_1") (pintype "input"))
      (node (ref "U2") (pin "10") (pinfunction "C1_10") (pintype "unspecified"))
    )
    (net (code "31") (name "Net-(U5-CPOUT)") (class "Default")
      (node (ref "C27") (pin "1") (pinfunction "1_1") (pintype "input"))
      (node (ref "U5") (pin "20") (pinfunction "CPOUT_20") (pintype "unspecified"))
    )
    (net (code "32") (name "Net-(U5-REGOUT)") (class "Default")
      (node (ref "C25") (pin "2") (pinfunction "2_2") (pintype "input"))
      (node (ref "U5") (pin "10") (pinfunction "REGOUT_10") (pintype "unspecified"))
    )
    (net (code "33") (name "Net-(USB1-DN1)") (class "Default")
      (node (ref "R8") (pin "2") (pinfunction "2_2") (pintype "input"))
      (node (ref "USB1") (pin "A7") (pinfunction "DN1_A7") (pintype "unspecified"))
    )
    (net (code "34") (name "Net-(USB1-DP1)") (class "Default")
      (node (ref "R7") (pin "2") (pinfunction "2_2") (pintype "input"))
      (node (ref "USB1") (pin "A6") (pinfunction "DP1_A6") (pintype "unspecified"))
    )
    (net (code "35") (name "OSC_IN") (class "Default")
      (node (ref "U1") (pin "12") (pinfunction "PH0-OSC_IN(PH0)_12") (pintype "bidirectional"))
      (node (ref "X1") (pin "2") (pinfunction "GND_2") (pintype "input"))
    )
    (net (code "36") (name "OSC_OUT") (class "Default")
      (node (ref "U1") (pin "13") (pinfunction "PH1-OSC_OUT(PH1)_13") (pintype "bidirectional"))
      (node (ref "X1") (pin "1") (pinfunction "1_1") (pintype "input"))
    )
    (net (code "37") (name "OTG_FS_DM") (class "Default")
      (node (ref "D2") (pin "3") (pinfunction "3_3") (pintype "input"))
      (node (ref "U1") (pin "70") (pinfunction "PA11_70") (pintype "bidirectional"))
    )
    (net (code "38") (name "OTG_FS_DP") (class "Default")
      (node (ref "D2") (pin "1") (pinfunction "1_1") (pintype "input"))
      (node (ref "U1") (pin "71") (pinfunction "PA12_71") (pintype "bidirectional"))
    )
    (net (code "39") (name "SPI1_MISO") (class "Default")
      (node (ref "CN1") (pin "4") (pinfunction "4_4") (pintype "unspecified"))
      (node (ref "U1") (pin "31") (pinfunction "PA6_31") (pintype "bidirectional"))
    )
    (net (code "40") (name "SPI1_MOSI") (class "Default")
      (node (ref "CN2") (pin "3") (pinfunction "3_3") (pintype "unspecified"))
      (node (ref "U1") (pin "32") (pinfunction "PA7_32") (pintype "bidirectional"))
    )
    (net (code "41") (name "SPI1_NSS") (class "Default")
      (node (ref "CN2") (pin "2") (pinfunction "2_2") (pintype "unspecified"))
      (node (ref "U1") (pin "29") (pinfunction "PA4_29") (pintype "bidirectional"))
    )
    (net (code "42") (name "SPI1_SCK") (class "Default")
      (node (ref "CN1") (pin "3") (pinfunction "3_3") (pintype "unspecified"))
      (node (ref "U1") (pin "30") (pinfunction "PA5_30") (pintype "bidirectional"))
    )
    (net (code "43") (name "SPI2_MISO") (class "Default")
      (node (ref "U1") (pin "53") (pinfunction "PB14_53") (pintype "bidirectional"))
      (node (ref "U6") (pin "5") (pinfunction "SDO_5") (pintype "unspecified"))
    )
    (net (code "44") (name "SPI2_MOSI") (class "Default")
      (node (ref "U1") (pin "54") (pinfunction "PB15_54") (pintype "bidirectional"))
      (node (ref "U6") (pin "3") (pinfunction "SDI_3") (pintype "unspecified"))
    )
    (net (code "45") (name "SPI2_NSS") (class "Default")
      (node (ref "U1") (pin "51") (pinfunction "PB12_51") (pintype "bidirectional"))
      (node (ref "U6") (pin "2") (pinfunction "CSB_2") (pintype "unspecified"))
    )
    (net (code "46") (name "SPI2_SCK") (class "Default")
      (node (ref "U1") (pin "52") (pinfunction "PB13_52") (pintype "bidirectional"))
      (node (ref "U6") (pin "4") (pinfunction "SCK_4") (pintype "unspecified"))
    )
    (net (code "47") (name "SWCLK") (class "Default")
      (node (ref "H5") (pin "1") (pinfunction "1_1") (pintype "unspecified"))
      (node (ref "R9") (pin "1") (pinfunction "1_1") (pintype "input"))
      (node (ref "U1") (pin "76") (pinfunction "PA14(JTCK-SWCLK)_76") (pintype "bidirectional"))
    )
    (net (code "48") (name "SWDIO") (class "Default")
      (node (ref "H5") (pin "2") (pinfunction "2_2") (pintype "unspecified"))
      (node (ref "R10") (pin "1") (pinfunction "1_1") (pintype "input"))
      (node (ref "U1") (pin "72") (pinfunction "PA13(JTMS-SWDIO)_72") (pintype "bidirectional"))
    )
    (net (code "49") (name "TIM4_CH1") (class "Default")
      (node (ref "H1") (pin "1") (pinfunction "1_1") (pintype "unspecified"))
      (node (ref "U1") (pin "59") (pinfunction "PD12_59") (pintype "bidirectional"))
    )
    (net (code "50") (name "TIM4_CH2") (class "Default")
      (node (ref "H2") (pin "1") (pinfunction "1_1") (pintype "unspecified"))
      (node (ref "U1") (pin "60") (pinfunction "PD13_60") (pintype "bidirectional"))
    )
    (net (code "51") (name "TIM4_CH3") (class "Default")
      (node (ref "H3") (pin "1") (pinfunction "1_1") (pintype "unspecified"))
      (node (ref "U1") (pin "61") (pinfunction "PD14_61") (pintype "bidirectional"))
    )
    (net (code "52") (name "TIM4_CH4") (class "Default")
      (node (ref "H4") (pin "1") (pinfunction "1_1") (pintype "unspecified"))
      (node (ref "U1") (pin "62") (pinfunction "PD15_62") (pintype "bidirectional"))
    )
    (net (code "53") (name "TIM9_CH1_RGB") (class "Default")
      (node (ref "LED2") (pin "2") (pinfunction "DOU_2") (pintype "unspecified"))
      (node (ref "U1") (pin "4") (pinfunction "PE5_4") (pintype "bidirectional"))
    )
    (net (code "54") (name "UART5_RX") (class "Default")
      (node (ref "CN5") (pin "1") (pinfunction "1_1") (pintype "unspecified"))
      (node (ref "U1") (pin "83") (pinfunction "PD2_83") (pintype "bidirectional"))
    )
    (net (code "55") (name "UART5_TX") (class "Default")
      (node (ref "CN5") (pin "2") (pinfunction "2_2") (pintype "unspecified"))
      (node (ref "U1") (pin "80") (pinfunction "PC12_80") (pintype "bidirectional"))
    )
    (net (code "56") (name "USART2_RX") (class "Default")
      (node (ref "CN3") (pin "1") (pinfunction "1_1") (pintype "unspecified"))
      (node (ref "U1") (pin "26") (pinfunction "PA3_26") (pintype "bidirectional"))
    )
    (net (code "57") (name "USART2_TX") (class "Default")
      (node (ref "CN3") (pin "2") (pinfunction "2_2") (pintype "unspecified"))
      (node (ref "U1") (pin "25") (pinfunction "PA2_25") (pintype "bidirectional"))
    )
    (net (code "58") (name "USART3_RX") (class "Default")
      (node (ref "CN4") (pin "1") (pinfunction "1_1") (pintype "unspecified"))
      (node (ref "U1") (pin "56") (pinfunction "PD9_56") (pintype "bidirectional"))
    )
    (net (code "59") (name "USART3_TX") (class "Default")
      (node (ref "CN4") (pin "2") (pinfunction "2_2") (pintype "unspecified"))
      (node (ref "U1") (pin "55") (pinfunction "PD8_55") (pintype "bidirectional"))
    )
    (net (code "60") (name "VBAT") (class "Default")
      (node (ref "H8") (pin "1") (pinfunction "1_1") (pintype "input"))
      (node (ref "SW4") (pin "1") (pinfunction "1_1") (pintype "unspecified"))
    )
    (net (code "61") (name "unconnected-(LED2-DIN-Pad4)") (class "Default")
      (node (ref "LED2") (pin "4") (pinfunction "DIN_4") (pintype "unspecified+no_connect"))
    )
    (net (code "62") (name "unconnected-(SCREW1-Pad1)") (class "Default")
      (node (ref "SCREW1") (pin "1") (pinfunction "1_1") (pintype "input"))
    )
    (net (code "63") (name "unconnected-(SCREW2-Pad1)") (class "Default")
      (node (ref "SCREW2") (pin "1") (pinfunction "1_1") (pintype "input"))
    )
    (net (code "64") (name "unconnected-(SCREW3-Pad1)") (class "Default")
      (node (ref "SCREW3") (pin "1") (pinfunction "1_1") (pintype "input"))
    )
    (net (code "65") (name "unconnected-(SCREW4-Pad1)") (class "Default")
      (node (ref "SCREW4") (pin "1") (pinfunction "1_1") (pintype "input"))
    )
    (net (code "66") (name "unconnected-(U1A-PA0-WKUP(PA0)-Pad23)") (class "Default")
      (node (ref "U1") (pin "23") (pinfunction "PA0-WKUP(PA0)_23") (pintype "bidirectional+no_connect"))
    )
    (net (code "67") (name "unconnected-(U1A-PA8-Pad67)") (class "Default")
      (node (ref "U1") (pin "67") (pinfunction "PA8_67") (pintype "bidirectional+no_connect"))
    )
    (net (code "68") (name "unconnected-(U1A-PA9-Pad68)") (class "Default")
      (node (ref "U1") (pin "68") (pinfunction "PA9_68") (pintype "bidirectional+no_connect"))
    )
    (net (code "69") (name "unconnected-(U1A-PA10-Pad69)") (class "Default")
      (node (ref "U1") (pin "69") (pinfunction "PA10_69") (pintype "bidirectional+no_connect"))
    )
    (net (code "70") (name "unconnected-(U1A-PA15(JTDI)-Pad77)") (class "Default")
      (node (ref "U1") (pin "77") (pinfunction "PA15(JTDI)_77") (pintype "bidirectional+no_connect"))
    )
    (net (code "71") (name "unconnected-(U1A-PB0-Pad35)") (class "Default")
      (node (ref "U1") (pin "35") (pinfunction "PB0_35") (pintype "bidirectional+no_connect"))
    )
    (net (code "72") (name "unconnected-(U1A-PB1-Pad36)") (class "Default")
      (node (ref "U1") (pin "36") (pinfunction "PB1_36") (pintype "bidirectional+no_connect"))
    )
    (net (code "73") (name "unconnected-(U1A-PB3(JTDOTRACESWO)-Pad89)") (class "Default")
      (node (ref "U1") (pin "89") (pinfunction "PB3(JTDOTRACESWO)_89") (pintype "bidirectional+no_connect"))
    )
    (net (code "74") (name "unconnected-(U1A-PB4(NJTRST)-Pad90)") (class "Default")
      (node (ref "U1") (pin "90") (pinfunction "PB4(NJTRST)_90") (pintype "bidirectional+no_connect"))
    )
    (net (code "75") (name "unconnected-(U1A-PB5-Pad91)") (class "Default")
      (node (ref "U1") (pin "91") (pinfunction "PB5_91") (pintype "bidirectional+no_connect"))
    )
    (net (code "76") (name "unconnected-(U1A-PB6-Pad92)") (class "Default")
      (node (ref "U1") (pin "92") (pinfunction "PB6_92") (pintype "bidirectional+no_connect"))
    )
    (net (code "77") (name "unconnected-(U1A-PC0-Pad15)") (class "Default")
      (node (ref "U1") (pin "15") (pinfunction "PC0_15") (pintype "bidirectional+no_connect"))
    )
    (net (code "78") (name "unconnected-(U1A-PC1-Pad16)") (class "Default")
      (node (ref "U1") (pin "16") (pinfunction "PC1_16") (pintype "bidirectional+no_connect"))
    )
    (net (code "79") (name "unconnected-(U1A-PC2-Pad17)") (class "Default")
      (node (ref "U1") (pin "17") (pinfunction "PC2_17") (pintype "bidirectional+no_connect"))
    )
    (net (code "80") (name "unconnected-(U1A-PC3-Pad18)") (class "Default")
      (node (ref "U1") (pin "18") (pinfunction "PC3_18") (pintype "bidirectional+no_connect"))
    )
    (net (code "81") (name "unconnected-(U1A-PC5-Pad34)") (class "Default")
      (node (ref "U1") (pin "34") (pinfunction "PC5_34") (pintype "bidirectional+no_connect"))
    )
    (net (code "82") (name "unconnected-(U1A-PC6-Pad63)") (class "Default")
      (node (ref "U1") (pin "63") (pinfunction "PC6_63") (pintype "bidirectional+no_connect"))
    )
    (net (code "83") (name "unconnected-(U1A-PC7-Pad64)") (class "Default")
      (node (ref "U1") (pin "64") (pinfunction "PC7_64") (pintype "bidirectional+no_connect"))
    )
    (net (code "84") (name "unconnected-(U1A-PC8-Pad65)") (class "Default")
      (node (ref "U1") (pin "65") (pinfunction "PC8_65") (pintype "bidirectional+no_connect"))
    )
    (net (code "85") (name "unconnected-(U1A-PC9-Pad66)") (class "Default")
      (node (ref "U1") (pin "66") (pinfunction "PC9_66") (pintype "bidirectional+no_connect"))
    )
    (net (code "86") (name "unconnected-(U1A-PC10-Pad78)") (class "Default")
      (node (ref "U1") (pin "78") (pinfunction "PC10_78") (pintype "bidirectional+no_connect"))
    )
    (net (code "87") (name "unconnected-(U1A-PC11-Pad79)") (class "Default")
      (node (ref "U1") (pin "79") (pinfunction "PC11_79") (pintype "bidirectional+no_connect"))
    )
    (net (code "88") (name "unconnected-(U1A-PC13-Pad7)") (class "Default")
      (node (ref "U1") (pin "7") (pinfunction "PC13_7") (pintype "bidirectional+no_connect"))
    )
    (net (code "89") (name "unconnected-(U1A-PC14-OSC32_IN(PC14)-Pad8)") (class "Default")
      (node (ref "U1") (pin "8") (pinfunction "PC14-OSC32_IN(PC14)_8") (pintype "bidirectional+no_connect"))
    )
    (net (code "90") (name "unconnected-(U1A-PC15-OSC32_OUT(PC15)-Pad9)") (class "Default")
      (node (ref "U1") (pin "9") (pinfunction "PC15-OSC32_OUT(PC15)_9") (pintype "bidirectional+no_connect"))
    )
    (net (code "91") (name "unconnected-(U1A-PD3-Pad84)") (class "Default")
      (node (ref "U1") (pin "84") (pinfunction "PD3_84") (pintype "bidirectional+no_connect"))
    )
    (net (code "92") (name "unconnected-(U1A-PD4-Pad85)") (class "Default")
      (node (ref "U1") (pin "85") (pinfunction "PD4_85") (pintype "bidirectional+no_connect"))
    )
    (net (code "93") (name "unconnected-(U1A-PD5-Pad86)") (class "Default")
      (node (ref "U1") (pin "86") (pinfunction "PD5_86") (pintype "bidirectional+no_connect"))
    )
    (net (code "94") (name "unconnected-(U1A-PD6-Pad87)") (class "Default")
      (node (ref "U1") (pin "87") (pinfunction "PD6_87") (pintype "bidirectional+no_connect"))
    )
    (net (code "95") (name "unconnected-(U1A-PD7-Pad88)") (class "Default")
      (node (ref "U1") (pin "88") (pinfunction "PD7_88") (pintype "bidirectional+no_connect"))
    )
    (net (code "96") (name "unconnected-(U1A-PD10-Pad57)") (class "Default")
      (node (ref "U1") (pin "57") (pinfunction "PD10_57") (pintype "bidirectional+no_connect"))
    )
    (net (code "97") (name "unconnected-(U1A-PD11-Pad58)") (class "Default")
      (node (ref "U1") (pin "58") (pinfunction "PD11_58") (pintype "bidirectional+no_connect"))
    )
    (net (code "98") (name "unconnected-(U1A-PE0-Pad97)") (class "Default")
      (node (ref "U1") (pin "97") (pinfunction "PE0_97") (pintype "bidirectional+no_connect"))
    )
    (net (code "99") (name "unconnected-(U1A-PE1-Pad98)") (class "Default")
      (node (ref "U1") (pin "98") (pinfunction "PE1_98") (pintype "bidirectional+no_connect"))
    )
    (net (code "100") (name "unconnected-(U1A-PE2-Pad1)") (class "Default")
      (node (ref "U1") (pin "1") (pinfunction "PE2_1") (pintype "bidirectional+no_connect"))
    )
    (net (code "101") (name "unconnected-(U1A-PE3-Pad2)") (class "Default")
      (node (ref "U1") (pin "2") (pinfunction "PE3_2") (pintype "bidirectional+no_connect"))
    )
    (net (code "102") (name "unconnected-(U1A-PE4-Pad3)") (class "Default")
      (node (ref "U1") (pin "3") (pinfunction "PE4_3") (pintype "bidirectional+no_connect"))
    )
    (net (code "103") (name "unconnected-(U1A-PE6-Pad5)") (class "Default")
      (node (ref "U1") (pin "5") (pinfunction "PE6_5") (pintype "bidirectional+no_connect"))
    )
    (net (code "104") (name "unconnected-(U1A-PE7-Pad38)") (class "Default")
      (node (ref "U1") (pin "38") (pinfunction "PE7_38") (pintype "bidirectional+no_connect"))
    )
    (net (code "105") (name "unconnected-(U1A-PE8-Pad39)") (class "Default")
      (node (ref "U1") (pin "39") (pinfunction "PE8_39") (pintype "bidirectional+no_connect"))
    )
    (net (code "106") (name "unconnected-(U1A-PE9-Pad40)") (class "Default")
      (node (ref "U1") (pin "40") (pinfunction "PE9_40") (pintype "bidirectional+no_connect"))
    )
    (net (code "107") (name "unconnected-(U1A-PE10-Pad41)") (class "Default")
      (node (ref "U1") (pin "41") (pinfunction "PE10_41") (pintype "bidirectional+no_connect"))
    )
    (net (code "108") (name "unconnected-(U1A-PE11-Pad42)") (class "Default")
      (node (ref "U1") (pin "42") (pinfunction "PE11_42") (pintype "bidirectional+no_connect"))
    )
    (net (code "109") (name "unconnected-(U1A-PE12-Pad43)") (class "Default")
      (node (ref "U1") (pin "43") (pinfunction "PE12_43") (pintype "bidirectional+no_connect"))
    )
    (net (code "110") (name "unconnected-(U1A-PE13-Pad44)") (class "Default")
      (node (ref "U1") (pin "44") (pinfunction "PE13_44") (pintype "bidirectional+no_connect"))
    )
    (net (code "111") (name "unconnected-(U1A-PE14-Pad45)") (class "Default")
      (node (ref "U1") (pin "45") (pinfunction "PE14_45") (pintype "bidirectional+no_connect"))
    )
    (net (code "112") (name "unconnected-(U1A-PE15-Pad46)") (class "Default")
      (node (ref "U1") (pin "46") (pinfunction "PE15_46") (pintype "bidirectional+no_connect"))
    )
    (net (code "113") (name "unconnected-(U2-CAD0-Pad5)") (class "Default")
      (node (ref "U2") (pin "5") (pinfunction "CAD0_5") (pintype "unspecified+no_connect"))
    )
    (net (code "114") (name "unconnected-(U2-CAD1-Pad6)") (class "Default")
      (node (ref "U2") (pin "6") (pinfunction "CAD1_6") (pintype "unspecified+no_connect"))
    )
    (net (code "115") (name "unconnected-(U2-DRDY-Pad15)") (class "Default")
      (node (ref "U2") (pin "15") (pinfunction "DRDY_15") (pintype "unspecified+no_connect"))
    )
    (net (code "116") (name "unconnected-(U2-NC-Pad3)") (class "Default")
      (node (ref "U2") (pin "3") (pinfunction "NC_3") (pintype "unspecified+no_connect"))
    )
    (net (code "117") (name "unconnected-(U2-NC-Pad4)") (class "Default")
      (node (ref "U2") (pin "4") (pinfunction "NC_4") (pintype "unspecified+no_connect"))
    )
    (net (code "118") (name "unconnected-(U2-NC-Pad8)") (class "Default")
      (node (ref "U2") (pin "8") (pinfunction "NC_8") (pintype "unspecified+no_connect"))
    )
    (net (code "119") (name "unconnected-(U2-NC-Pad12)") (class "Default")
      (node (ref "U2") (pin "12") (pinfunction "NC_12") (pintype "unspecified+no_connect"))
    )
    (net (code "120") (name "unconnected-(U2-VPP-Pad7)") (class "Default")
      (node (ref "U2") (pin "7") (pinfunction "VPP_7") (pintype "unspecified+no_connect"))
    )
    (net (code "121") (name "unconnected-(U3-BYP-Pad4)") (class "Default")
      (node (ref "U3") (pin "4") (pinfunction "BYP_4") (pintype "unspecified+no_connect"))
    )
    (net (code "122") (name "unconnected-(U4-SHDN-Pad5)") (class "Default")
      (node (ref "U4") (pin "5") (pinfunction "SHDN_5") (pintype "unspecified+no_connect"))
    )
    (net (code "123") (name "unconnected-(U5-AUX_CL-Pad7)") (class "Default")
      (node (ref "U5") (pin "7") (pinfunction "AUX_CL_7") (pintype "unspecified+no_connect"))
    )
    (net (code "124") (name "unconnected-(U5-AUX_DA-Pad6)") (class "Default")
      (node (ref "U5") (pin "6") (pinfunction "AUX_DA_6") (pintype "unspecified+no_connect"))
    )
    (net (code "125") (name "unconnected-(U5-INT-Pad12)") (class "Default")
      (node (ref "U5") (pin "12") (pinfunction "INT_12") (pintype "unspecified+no_connect"))
    )
    (net (code "126") (name "unconnected-(U5-NC-Pad2)") (class "Default")
      (node (ref "U5") (pin "2") (pinfunction "NC_2") (pintype "unspecified+no_connect"))
    )
    (net (code "127") (name "unconnected-(U5-NC-Pad3)") (class "Default")
      (node (ref "U5") (pin "3") (pinfunction "NC_3") (pintype "unspecified+no_connect"))
    )
    (net (code "128") (name "unconnected-(U5-NC-Pad4)") (class "Default")
      (node (ref "U5") (pin "4") (pinfunction "NC_4") (pintype "unspecified+no_connect"))
    )
    (net (code "129") (name "unconnected-(U5-NC-Pad5)") (class "Default")
      (node (ref "U5") (pin "5") (pinfunction "NC_5") (pintype "unspecified+no_connect"))
    )
    (net (code "130") (name "unconnected-(U5-NC-Pad14)") (class "Default")
      (node (ref "U5") (pin "14") (pinfunction "NC_14") (pintype "unspecified+no_connect"))
    )
    (net (code "131") (name "unconnected-(U5-NC-Pad15)") (class "Default")
      (node (ref "U5") (pin "15") (pinfunction "NC_15") (pintype "unspecified+no_connect"))
    )
    (net (code "132") (name "unconnected-(U5-NC-Pad16)") (class "Default")
      (node (ref "U5") (pin "16") (pinfunction "NC_16") (pintype "unspecified+no_connect"))
    )
    (net (code "133") (name "unconnected-(U5-NC-Pad17)") (class "Default")
      (node (ref "U5") (pin "17") (pinfunction "NC_17") (pintype "unspecified+no_connect"))
    )
    (net (code "134") (name "unconnected-(U5-RESV-Pad19)") (class "Default")
      (node (ref "U5") (pin "19") (pinfunction "RESV_19") (pintype "unspecified+no_connect"))
    )
    (net (code "135") (name "unconnected-(U5-RESV-Pad21)") (class "Default")
      (node (ref "U5") (pin "21") (pinfunction "RESV_21") (pintype "unspecified+no_connect"))
    )
    (net (code "136") (name "unconnected-(U5-RESV-Pad22)") (class "Default")
      (node (ref "U5") (pin "22") (pinfunction "RESV_22") (pintype "unspecified+no_connect"))
    )
    (net (code "137") (name "unconnected-(U7-Pad2)") (class "Default")
      (node (ref "U7") (pin "2") (pinfunction "2_2") (pintype "unspecified+no_connect"))
    )
    (net (code "138") (name "unconnected-(U7-Pad4)") (class "Default")
      (node (ref "U7") (pin "4") (pinfunction "4_4") (pintype "unspecified+no_connect"))
    )
    (net (code "139") (name "unconnected-(USB1-CC1-PadA5)") (class "Default")
      (node (ref "USB1") (pin "A5") (pinfunction "CC1_A5") (pintype "unspecified+no_connect"))
    )
    (net (code "140") (name "unconnected-(USB1-CC2-PadB5)") (class "Default")
      (node (ref "USB1") (pin "B5") (pinfunction "CC2_B5") (pintype "unspecified+no_connect"))
    )
    (net (code "141") (name "unconnected-(USB1-DN2-PadB7)") (class "Default")
      (node (ref "USB1") (pin "B7") (pinfunction "DN2_B7") (pintype "unspecified+no_connect"))
    )
    (net (code "142") (name "unconnected-(USB1-DP2-PadB6)") (class "Default")
      (node (ref "USB1") (pin "B6") (pinfunction "DP2_B6") (pintype "unspecified+no_connect"))
    )
    (net (code "143") (name "unconnected-(USB1-SUB1-PadA8)") (class "Default")
      (node (ref "USB1") (pin "A8") (pinfunction "SUB1_A8") (pintype "unspecified+no_connect"))
    )
    (net (code "144") (name "unconnected-(USB1-SUB2-PadB8)") (class "Default")
      (node (ref "USB1") (pin "B8") (pinfunction "SUB2_B8") (pintype "unspecified+no_connect"))
    )
  )
)
